# 18_HD4_PUMP.net
KiCad netlist of a schematic drawn in Altium Designer
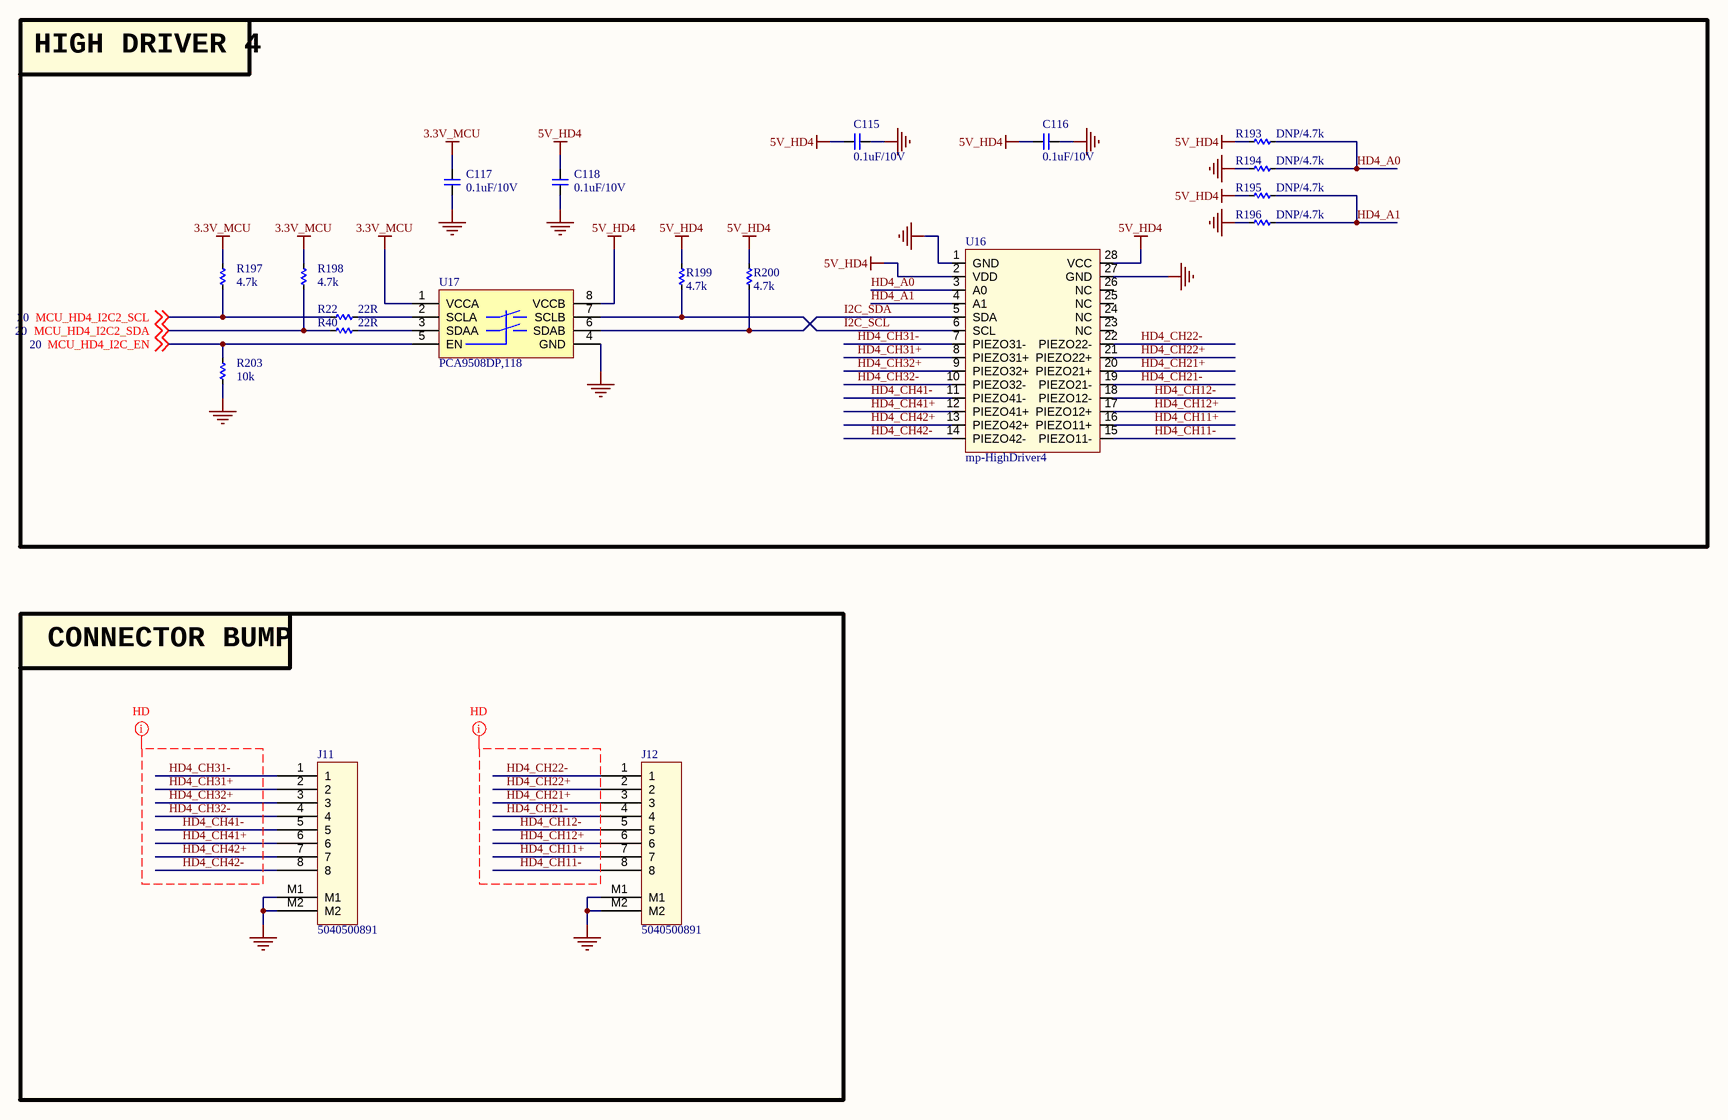
[diagram p0: 18_HD4_PUMP.SchDoc]

(export (version "E")
  (design (tool "Eeschema 10.0.6"))
  (components
    (comp (ref "C115")
      (value "0.1uF/10V")
      (footprint "CAP_C_1005X60")
      (description "CAP")
      (libsource (lib "LABLIB") (part "_CAP_C_2"))
    )
    (comp (ref "C116")
      (value "0.1uF/10V")
      (footprint "CAP_C_1005X60")
      (description "CAP")
      (libsource (lib "LABLIB") (part "_CAP_C_2"))
    )
    (comp (ref "C117")
      (value "0.1uF/10V")
      (footprint "CAP_C_1005X60")
      (description "CAP")
      (libsource (lib "LABLIB") (part "_CAP_C_2"))
    )
    (comp (ref "C118")
      (value "0.1uF/10V")
      (footprint "CAP_C_1005X60")
      (description "CAP")
      (libsource (lib "LABLIB") (part "_CAP_C_2"))
    )
    (comp (ref "J11")
      (value "5040500891")
      (footprint "MOLEX_5040500891")
      (libsource (lib "LABLIB") (part "Header 8x1_2M"))
    )
    (comp (ref "J12")
      (value "5040500891")
      (footprint "MOLEX_5040500891")
      (libsource (lib "LABLIB") (part "Header 8x1_2M"))
    )
    (comp (ref "R22")
      (value "22R")
      (footprint "RES_C_1005X40")
      (description "RES")
      (libsource (lib "LABLIB") (part "_RES_B_2"))
    )
    (comp (ref "R40")
      (value "22R")
      (footprint "RES_C_1005X40")
      (description "RES")
      (libsource (lib "LABLIB") (part "_RES_B_2"))
    )
    (comp (ref "R193")
      (value "DNP/4.7k")
      (footprint "RES_C_1005X40")
      (description "RES")
      (libsource (lib "LABLIB") (part "_RES_B_2"))
    )
    (comp (ref "R194")
      (value "DNP/4.7k")
      (footprint "RES_C_1005X40")
      (description "RES")
      (libsource (lib "LABLIB") (part "_RES_B_2"))
    )
    (comp (ref "R195")
      (value "DNP/4.7k")
      (footprint "RES_C_1005X40")
      (description "RES")
      (libsource (lib "LABLIB") (part "_RES_B_2"))
    )
    (comp (ref "R196")
      (value "DNP/4.7k")
      (footprint "RES_C_1005X40")
      (description "RES")
      (libsource (lib "LABLIB") (part "_RES_B_2"))
    )
    (comp (ref "R197")
      (value "4.7k")
      (footprint "RES_C_1005X40")
      (description "RES")
      (libsource (lib "LABLIB") (part "_RES_B_2"))
    )
    (comp (ref "R198")
      (value "4.7k")
      (footprint "RES_C_1005X40")
      (description "RES")
      (libsource (lib "LABLIB") (part "_RES_B_2"))
    )
    (comp (ref "R199")
      (value "4.7k")
      (footprint "RES_C_1005X40")
      (description "RES")
      (libsource (lib "LABLIB") (part "_RES_B_2"))
    )
    (comp (ref "R200")
      (value "4.7k")
      (footprint "RES_C_1005X40")
      (description "RES")
      (libsource (lib "LABLIB") (part "_RES_B_2"))
    )
    (comp (ref "R203")
      (value "10k")
      (footprint "RES_C_1005X40")
      (description "RES")
      (libsource (lib "LABLIB") (part "_RES_B_2"))
    )
    (comp (ref "U16")
      (value "mp-HighDriver4")
      (footprint "MP_HIGHDRIVER4")
      (libsource (lib "new_component") (part "mp_HighDriver4"))
    )
    (comp (ref "U17")
      (value "PCA9508DP,118")
      (footprint "TSOP8")
      (libsource (lib "EXP_HW_V3") (part "PCA9508DP,118"))
    )
  )
  (nets
    (net (code "1") (name "/HD4_A0") (class "Default")
      (node (ref "R193") (pin "2") (pinfunction "2_2") (pintype "passive"))
      (node (ref "R194") (pin "2") (pinfunction "2_2") (pintype "passive"))
      (node (ref "U16") (pin "3") (pinfunction "A0_3") (pintype "passive"))
    )
    (net (code "2") (name "/HD4_A1") (class "Default")
      (node (ref "R195") (pin "2") (pinfunction "2_2") (pintype "passive"))
      (node (ref "R196") (pin "2") (pinfunction "2_2") (pintype "passive"))
      (node (ref "U16") (pin "4") (pinfunction "A1_4") (pintype "passive"))
    )
    (net (code "3") (name "/HD4_CH11+") (class "Default")
      (node (ref "J12") (pin "7") (pinfunction "7_7") (pintype "passive"))
      (node (ref "U16") (pin "16") (pinfunction "PIEZO11+_16") (pintype "passive"))
    )
    (net (code "4") (name "/HD4_CH11-") (class "Default")
      (node (ref "J12") (pin "8") (pinfunction "8_8") (pintype "passive"))
      (node (ref "U16") (pin "15") (pinfunction "PIEZO11-_15") (pintype "passive"))
    )
    (net (code "5") (name "/HD4_CH12+") (class "Default")
      (node (ref "J12") (pin "6") (pinfunction "6_6") (pintype "passive"))
      (node (ref "U16") (pin "17") (pinfunction "PIEZO12+_17") (pintype "passive"))
    )
    (net (code "6") (name "/HD4_CH12-") (class "Default")
      (node (ref "J12") (pin "5") (pinfunction "5_5") (pintype "passive"))
      (node (ref "U16") (pin "18") (pinfunction "PIEZO12-_18") (pintype "passive"))
    )
    (net (code "7") (name "/HD4_CH21+") (class "Default")
      (node (ref "J12") (pin "3") (pinfunction "3_3") (pintype "passive"))
      (node (ref "U16") (pin "20") (pinfunction "PIEZO21+_20") (pintype "passive"))
    )
    (net (code "8") (name "/HD4_CH21-") (class "Default")
      (node (ref "J12") (pin "4") (pinfunction "4_4") (pintype "passive"))
      (node (ref "U16") (pin "19") (pinfunction "PIEZO21-_19") (pintype "passive"))
    )
    (net (code "9") (name "/HD4_CH22+") (class "Default")
      (node (ref "J12") (pin "2") (pinfunction "2_2") (pintype "passive"))
      (node (ref "U16") (pin "21") (pinfunction "PIEZO22+_21") (pintype "passive"))
    )
    (net (code "10") (name "/HD4_CH22-") (class "Default")
      (node (ref "J12") (pin "1") (pinfunction "1_1") (pintype "passive"))
      (node (ref "U16") (pin "22") (pinfunction "PIEZO22-_22") (pintype "passive"))
    )
    (net (code "11") (name "/HD4_CH31+") (class "Default")
      (node (ref "J11") (pin "2") (pinfunction "2_2") (pintype "passive"))
      (node (ref "U16") (pin "8") (pinfunction "PIEZO31+_8") (pintype "passive"))
    )
    (net (code "12") (name "/HD4_CH31-") (class "Default")
      (node (ref "J11") (pin "1") (pinfunction "1_1") (pintype "passive"))
      (node (ref "U16") (pin "7") (pinfunction "PIEZO31-_7") (pintype "passive"))
    )
    (net (code "13") (name "/HD4_CH32+") (class "Default")
      (node (ref "J11") (pin "3") (pinfunction "3_3") (pintype "passive"))
      (node (ref "U16") (pin "9") (pinfunction "PIEZO32+_9") (pintype "passive"))
    )
    (net (code "14") (name "/HD4_CH32-") (class "Default")
      (node (ref "J11") (pin "4") (pinfunction "4_4") (pintype "passive"))
      (node (ref "U16") (pin "10") (pinfunction "PIEZO32-_10") (pintype "passive"))
    )
    (net (code "15") (name "/HD4_CH41+") (class "Default")
      (node (ref "J11") (pin "6") (pinfunction "6_6") (pintype "passive"))
      (node (ref "U16") (pin "12") (pinfunction "PIEZO41+_12") (pintype "passive"))
    )
    (net (code "16") (name "/HD4_CH41-") (class "Default")
      (node (ref "J11") (pin "5") (pinfunction "5_5") (pintype "passive"))
      (node (ref "U16") (pin "11") (pinfunction "PIEZO41-_11") (pintype "passive"))
    )
    (net (code "17") (name "/HD4_CH42+") (class "Default")
      (node (ref "J11") (pin "7") (pinfunction "7_7") (pintype "passive"))
      (node (ref "U16") (pin "13") (pinfunction "PIEZO42+_13") (pintype "passive"))
    )
    (net (code "18") (name "/HD4_CH42-") (class "Default")
      (node (ref "J11") (pin "8") (pinfunction "8_8") (pintype "passive"))
      (node (ref "U16") (pin "14") (pinfunction "PIEZO42-_14") (pintype "passive"))
    )
    (net (code "19") (name "/I2C_SCL") (class "Default")
      (node (ref "R199") (pin "2") (pinfunction "2_2") (pintype "passive"))
      (node (ref "U16") (pin "6") (pinfunction "SCL_6") (pintype "passive"))
      (node (ref "U17") (pin "7") (pinfunction "SCLB_7") (pintype "passive"))
    )
    (net (code "20") (name "/I2C_SDA") (class "Default")
      (node (ref "R200") (pin "2") (pinfunction "2_2") (pintype "passive"))
      (node (ref "U16") (pin "5") (pinfunction "SDA_5") (pintype "passive"))
      (node (ref "U17") (pin "6") (pinfunction "SDAB_6") (pintype "passive"))
    )
    (net (code "21") (name "3.3V_MCU") (class "Default")
      (node (ref "C117") (pin "2") (pinfunction "2_2") (pintype "passive"))
      (node (ref "R197") (pin "1") (pinfunction "1_1") (pintype "passive"))
      (node (ref "R198") (pin "1") (pinfunction "1_1") (pintype "passive"))
      (node (ref "U17") (pin "1") (pinfunction "VCCA_1") (pintype "passive"))
    )
    (net (code "22") (name "5V_HD4") (class "Default")
      (node (ref "C115") (pin "2") (pinfunction "2_2") (pintype "passive"))
      (node (ref "C116") (pin "2") (pinfunction "2_2") (pintype "passive"))
      (node (ref "C118") (pin "2") (pinfunction "2_2") (pintype "passive"))
      (node (ref "R193") (pin "1") (pinfunction "1_1") (pintype "passive"))
      (node (ref "R195") (pin "1") (pinfunction "1_1") (pintype "passive"))
      (node (ref "R199") (pin "1") (pinfunction "1_1") (pintype "passive"))
      (node (ref "R200") (pin "1") (pinfunction "1_1") (pintype "passive"))
      (node (ref "U16") (pin "2") (pinfunction "VDD_2") (pintype "power_in"))
      (node (ref "U16") (pin "28") (pinfunction "VCC_28") (pintype "power_in"))
      (node (ref "U17") (pin "8") (pinfunction "VCCB_8") (pintype "passive"))
    )
    (net (code "23") (name "GND") (class "Default")
      (node (ref "C115") (pin "1") (pinfunction "1_1") (pintype "passive"))
      (node (ref "C116") (pin "1") (pinfunction "1_1") (pintype "passive"))
      (node (ref "C117") (pin "1") (pinfunction "1_1") (pintype "passive"))
      (node (ref "C118") (pin "1") (pinfunction "1_1") (pintype "passive"))
      (node (ref "J11") (pin "M1") (pinfunction "M1_M1") (pintype "passive"))
      (node (ref "J11") (pin "M2") (pinfunction "M2_M2") (pintype "passive"))
      (node (ref "J12") (pin "M1") (pinfunction "M1_M1") (pintype "passive"))
      (node (ref "J12") (pin "M2") (pinfunction "M2_M2") (pintype "passive"))
      (node (ref "R194") (pin "1") (pinfunction "1_1") (pintype "passive"))
      (node (ref "R196") (pin "1") (pinfunction "1_1") (pintype "passive"))
      (node (ref "R203") (pin "2") (pinfunction "2_2") (pintype "passive"))
      (node (ref "U16") (pin "1") (pinfunction "GND_1") (pintype "power_in"))
      (node (ref "U16") (pin "27") (pinfunction "GND_27") (pintype "power_in"))
      (node (ref "U17") (pin "4") (pinfunction "GND_4") (pintype "passive"))
    )
    (net (code "24") (name "MCU_HD4_I2C2_SCL") (class "Default")
      (node (ref "R197") (pin "2") (pinfunction "2_2") (pintype "passive"))
      (node (ref "R22") (pin "1") (pinfunction "1_1") (pintype "passive"))
    )
    (net (code "25") (name "MCU_HD4_I2C2_SDA") (class "Default")
      (node (ref "R198") (pin "2") (pinfunction "2_2") (pintype "passive"))
      (node (ref "R40") (pin "1") (pinfunction "1_1") (pintype "passive"))
    )
    (net (code "26") (name "MCU_HD4_I2C_EN") (class "Default")
      (node (ref "R203") (pin "1") (pinfunction "1_1") (pintype "passive"))
      (node (ref "U17") (pin "5") (pinfunction "EN_5") (pintype "passive"))
    )
    (net (code "27") (name "Net-(U17-SCLA)") (class "Default")
      (node (ref "R22") (pin "2") (pinfunction "2_2") (pintype "passive"))
      (node (ref "U17") (pin "2") (pinfunction "SCLA_2") (pintype "passive"))
    )
    (net (code "28") (name "Net-(U17-SDAA)") (class "Default")
      (node (ref "R40") (pin "2") (pinfunction "2_2") (pintype "passive"))
      (node (ref "U17") (pin "3") (pinfunction "SDAA_3") (pintype "passive"))
    )
    (net (code "29") (name "unconnected-(U16-NC-Pad23)") (class "Default")
      (node (ref "U16") (pin "23") (pinfunction "NC_23") (pintype "passive"))
    )
    (net (code "30") (name "unconnected-(U16-NC-Pad24)") (class "Default")
      (node (ref "U16") (pin "24") (pinfunction "NC_24") (pintype "passive"))
    )
    (net (code "31") (name "unconnected-(U16-NC-Pad25)") (class "Default")
      (node (ref "U16") (pin "25") (pinfunction "NC_25") (pintype "passive"))
    )
    (net (code "32") (name "unconnected-(U16-NC-Pad26)") (class "Default")
      (node (ref "U16") (pin "26") (pinfunction "NC_26") (pintype "passive"))
    )
  )
)
